# rs232_mon.net
KiCad netlist of a schematic drawn in EAGLE
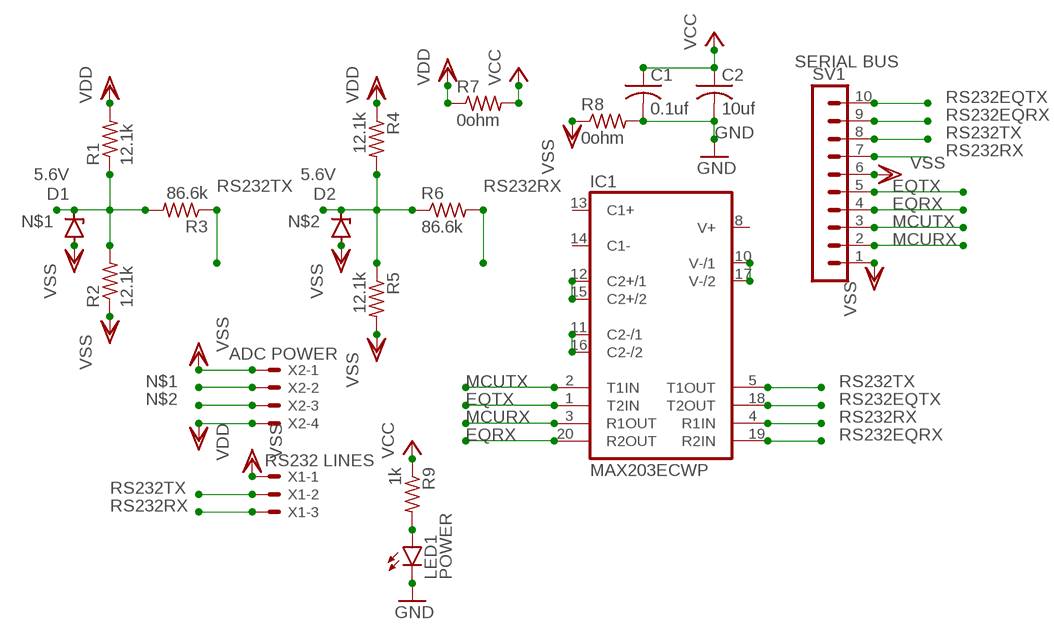
[diagram p0: schematic, sheet 1]

(export (version "E")
  (design (tool "Eeschema 10.0.6"))
  (components
    (comp (ref "C1")
      (value "0.1uf")
      (footprint "eagle-import:C0805")
      (libsource (lib "eagle-import") (part "C-USC0805"))
    )
    (comp (ref "C2")
      (value "10uf")
      (footprint "eagle-import:C0805")
      (libsource (lib "eagle-import") (part "C-USC0805"))
    )
    (comp (ref "D1")
      (value "5.6V")
      (footprint "eagle-import:DO34Z7")
      (libsource (lib "eagle-import") (part "ZENER-DIODEDO34-7"))
    )
    (comp (ref "D2")
      (value "5.6V")
      (footprint "eagle-import:DO34Z7")
      (libsource (lib "eagle-import") (part "ZENER-DIODEDO34-7"))
    )
    (comp (ref "IC1")
      (value "MAX203ECWP")
      (footprint "eagle-import:SO20L")
      (fields (field (name "MPN") "MAX203ECWP+G36"))
      (libsource (lib "eagle-import") (part "MAX203ECWP"))
    )
    (comp (ref "LED1")
      (value "POWER")
      (footprint "eagle-import:CHIP-LED0603")
      (libsource (lib "eagle-import") (part "LEDCHIP-LED0603"))
    )
    (comp (ref "R1")
      (value "12.1k")
      (footprint "eagle-import:R0805")
      (libsource (lib "eagle-import") (part "R-US_R0805"))
    )
    (comp (ref "R2")
      (value "12.1k")
      (footprint "eagle-import:R0805")
      (libsource (lib "eagle-import") (part "R-US_R0805"))
    )
    (comp (ref "R3")
      (value "86.6k")
      (footprint "eagle-import:R0805")
      (libsource (lib "eagle-import") (part "R-US_R0805"))
    )
    (comp (ref "R4")
      (value "12.1k")
      (footprint "eagle-import:R0805")
      (libsource (lib "eagle-import") (part "R-US_R0805"))
    )
    (comp (ref "R5")
      (value "12.1k")
      (footprint "eagle-import:R0805")
      (libsource (lib "eagle-import") (part "R-US_R0805"))
    )
    (comp (ref "R6")
      (value "86.6k")
      (footprint "eagle-import:R0805")
      (libsource (lib "eagle-import") (part "R-US_R0805"))
    )
    (comp (ref "R7")
      (value "0ohm")
      (footprint "eagle-import:R0805")
      (libsource (lib "eagle-import") (part "R-US_R0805"))
    )
    (comp (ref "R8")
      (value "0ohm")
      (footprint "eagle-import:R0805")
      (libsource (lib "eagle-import") (part "R-US_R0805"))
    )
    (comp (ref "R9")
      (value "1k")
      (footprint "eagle-import:R0805")
      (libsource (lib "eagle-import") (part "R-US_R0805"))
    )
    (comp (ref "SV1")
      (value "SERIAL BUS")
      (footprint "eagle-import:MA10-1")
      (libsource (lib "eagle-import") (part "MA10-1"))
    )
    (comp (ref "X1")
      (value "RS232 LINES")
      (footprint "eagle-import:22-23-2031")
      (fields (field (name "MF") "MOLEX") (field (name "MPN") "22-23-2031"))
      (libsource (lib "eagle-import") (part "22-23-2031"))
    )
    (comp (ref "X2")
      (value "ADC POWER")
      (footprint "eagle-import:22-23-2041")
      (fields (field (name "MF") "MOLEX") (field (name "MPN") "22-23-2041"))
      (libsource (lib "eagle-import") (part "22-23-2041"))
    )
  )
  (nets
    (net (code "1") (name "/EQRX") (class "Default")
      (node (ref "IC1") (pin "20") (pinfunction "R2OUT_20") (pintype "output"))
      (node (ref "SV1") (pin "4") (pinfunction "4_4") (pintype "passive"))
    )
    (net (code "2") (name "/EQTX") (class "Default")
      (node (ref "IC1") (pin "1") (pinfunction "T2IN_1") (pintype "input"))
      (node (ref "SV1") (pin "5") (pinfunction "5_5") (pintype "passive"))
    )
    (net (code "3") (name "/MCURX") (class "Default")
      (node (ref "IC1") (pin "3") (pinfunction "R1OUT_3") (pintype "output"))
      (node (ref "SV1") (pin "2") (pinfunction "2_2") (pintype "passive"))
    )
    (net (code "4") (name "/MCUTX") (class "Default")
      (node (ref "IC1") (pin "2") (pinfunction "T1IN_2") (pintype "input"))
      (node (ref "SV1") (pin "3") (pinfunction "3_3") (pintype "passive"))
    )
    (net (code "5") (name "/N$1") (class "Default")
      (node (ref "D1") (pin "C") (pinfunction "C_C") (pintype "passive"))
      (node (ref "R1") (pin "1") (pinfunction "1_1") (pintype "passive"))
      (node (ref "R2") (pin "2") (pinfunction "2_2") (pintype "passive"))
      (node (ref "R3") (pin "2") (pinfunction "2_2") (pintype "passive"))
      (node (ref "X2") (pin "2") (pinfunction "S_2") (pintype "passive"))
    )
    (net (code "6") (name "/N$2") (class "Default")
      (node (ref "D2") (pin "C") (pinfunction "C_C") (pintype "passive"))
      (node (ref "R4") (pin "2") (pinfunction "2_2") (pintype "passive"))
      (node (ref "R5") (pin "1") (pinfunction "1_1") (pintype "passive"))
      (node (ref "R6") (pin "1") (pinfunction "1_1") (pintype "passive"))
      (node (ref "X2") (pin "3") (pinfunction "S_3") (pintype "passive"))
    )
    (net (code "7") (name "/RS232EQRX") (class "Default")
      (node (ref "IC1") (pin "19") (pinfunction "R2IN_19") (pintype "input"))
      (node (ref "SV1") (pin "9") (pinfunction "9_9") (pintype "passive"))
    )
    (net (code "8") (name "/RS232EQTX") (class "Default")
      (node (ref "IC1") (pin "18") (pinfunction "T2OUT_18") (pintype "output"))
      (node (ref "SV1") (pin "10") (pinfunction "10_10") (pintype "passive"))
    )
    (net (code "9") (name "/RS232RX") (class "Default")
      (node (ref "IC1") (pin "4") (pinfunction "R1IN_4") (pintype "input"))
      (node (ref "R6") (pin "2") (pinfunction "2_2") (pintype "passive"))
      (node (ref "SV1") (pin "7") (pinfunction "7_7") (pintype "passive"))
      (node (ref "X1") (pin "3") (pinfunction "S_3") (pintype "passive"))
    )
    (net (code "10") (name "/RS232TX") (class "Default")
      (node (ref "IC1") (pin "5") (pinfunction "T1OUT_5") (pintype "output"))
      (node (ref "R3") (pin "1") (pinfunction "1_1") (pintype "passive"))
      (node (ref "SV1") (pin "8") (pinfunction "8_8") (pintype "passive"))
      (node (ref "X1") (pin "2") (pinfunction "S_2") (pintype "passive"))
    )
    (net (code "11") (name "GND") (class "Default")
      (node (ref "C1") (pin "2") (pinfunction "2_2") (pintype "passive"))
      (node (ref "C2") (pin "2") (pinfunction "2_2") (pintype "passive"))
      (node (ref "LED1") (pin "C") (pinfunction "C_C") (pintype "passive"))
      (node (ref "R8") (pin "2") (pinfunction "2_2") (pintype "passive"))
    )
    (net (code "12") (name "Net-(IC1A-C2+{slash}1)") (class "Default")
      (node (ref "IC1") (pin "12") (pinfunction "C2+/1_12") (pintype "passive"))
      (node (ref "IC1") (pin "15") (pinfunction "C2+/2_15") (pintype "passive"))
    )
    (net (code "13") (name "Net-(IC1A-C2-{slash}1)") (class "Default")
      (node (ref "IC1") (pin "11") (pinfunction "C2-/1_11") (pintype "passive"))
      (node (ref "IC1") (pin "16") (pinfunction "C2-/2_16") (pintype "passive"))
    )
    (net (code "14") (name "Net-(IC1A-V-{slash}1)") (class "Default")
      (node (ref "IC1") (pin "10") (pinfunction "V-/1_10") (pintype "passive"))
      (node (ref "IC1") (pin "17") (pinfunction "V-/2_17") (pintype "passive"))
    )
    (net (code "15") (name "Net-(LED1-PadA)") (class "Default")
      (node (ref "LED1") (pin "A") (pinfunction "A_A") (pintype "passive"))
      (node (ref "R9") (pin "2") (pinfunction "2_2") (pintype "passive"))
    )
    (net (code "16") (name "VCC") (class "Default")
      (node (ref "C1") (pin "1") (pinfunction "1_1") (pintype "passive"))
      (node (ref "C2") (pin "1") (pinfunction "1_1") (pintype "passive"))
      (node (ref "R7") (pin "2") (pinfunction "2_2") (pintype "passive"))
      (node (ref "R9") (pin "1") (pinfunction "1_1") (pintype "passive"))
    )
    (net (code "17") (name "VDD") (class "Default")
      (node (ref "R1") (pin "2") (pinfunction "2_2") (pintype "passive"))
      (node (ref "R4") (pin "1") (pinfunction "1_1") (pintype "passive"))
      (node (ref "R7") (pin "1") (pinfunction "1_1") (pintype "passive"))
      (node (ref "X2") (pin "4") (pinfunction "S_4") (pintype "passive"))
    )
    (net (code "18") (name "VSS") (class "Default")
      (node (ref "D1") (pin "A") (pinfunction "A_A") (pintype "passive"))
      (node (ref "D2") (pin "A") (pinfunction "A_A") (pintype "passive"))
      (node (ref "R2") (pin "1") (pinfunction "1_1") (pintype "passive"))
      (node (ref "R5") (pin "2") (pinfunction "2_2") (pintype "passive"))
      (node (ref "R8") (pin "1") (pinfunction "1_1") (pintype "passive"))
      (node (ref "SV1") (pin "1") (pinfunction "1_1") (pintype "passive"))
      (node (ref "SV1") (pin "6") (pinfunction "6_6") (pintype "passive"))
      (node (ref "X1") (pin "1") (pinfunction "S_1") (pintype "passive"))
      (node (ref "X2") (pin "1") (pinfunction "S_1") (pintype "passive"))
    )
    (net (code "19") (name "unconnected-(IC1A-C1+-Pad13)") (class "Default")
      (node (ref "IC1") (pin "13") (pinfunction "C1+_13") (pintype "passive"))
    )
    (net (code "20") (name "unconnected-(IC1A-C1--Pad14)") (class "Default")
      (node (ref "IC1") (pin "14") (pinfunction "C1-_14") (pintype "passive"))
    )
    (net (code "21") (name "unconnected-(IC1A-V+-Pad8)") (class "Default")
      (node (ref "IC1") (pin "8") (pinfunction "V+_8") (pintype "passive"))
    )
  )
)
